# Sensores.net
KiCad netlist of a schematic drawn in Altium Designer
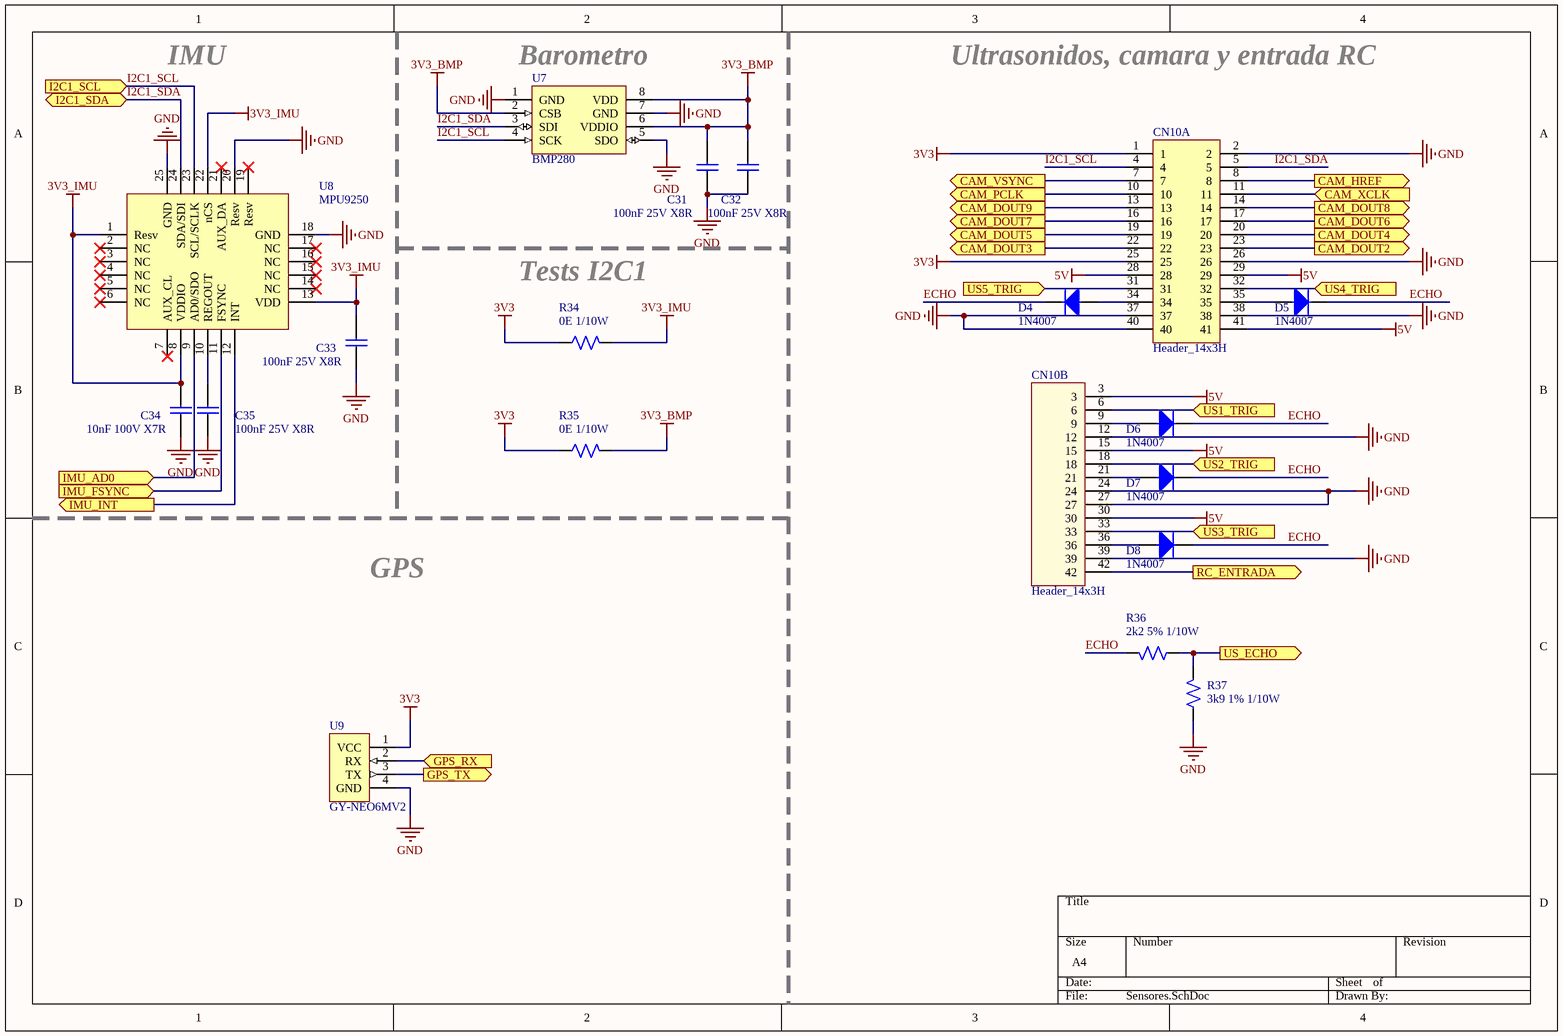
[diagram p0: Sensores.SchDoc]

(export (version "E")
  (design (tool "Eeschema 10.0.6"))
  (components
    (comp (ref "C31")
      (value "100nF 25V X8R")
      (footprint "C0603")
      (description "Capacitor de placas paralelas")
      (libsource (lib "HW_Dron_V2") (part "Capacitor"))
    )
    (comp (ref "C32")
      (value "100nF 25V X8R")
      (footprint "C0603")
      (description "Capacitor de placas paralelas")
      (libsource (lib "HW_Dron_V2") (part "Capacitor"))
    )
    (comp (ref "C33")
      (value "100nF 25V X8R")
      (footprint "C0603")
      (description "Capacitor de placas paralelas")
      (libsource (lib "HW_Dron_V2") (part "Capacitor"))
    )
    (comp (ref "C34")
      (value "10nF 100V X7R")
      (footprint "C0603")
      (description "Capacitor de placas paralelas")
      (libsource (lib "HW_Dron_V2") (part "Capacitor"))
    )
    (comp (ref "C35")
      (value "100nF 25V X8R")
      (footprint "C0603")
      (description "Capacitor de placas paralelas")
      (libsource (lib "HW_Dron_V2") (part "Capacitor"))
    )
    (comp (ref "CN10")
      (value "Header_14x3H")
      (footprint "HEADER_14x3H")
      (description "Header, 14x3-pin")
      (libsource (lib "HW_Dron_V2") (part "Header_14x3H"))
    )
    (comp (ref "D4")
      (value "1N4007")
      (footprint "SMA (DO-214AC)")
      (description "Diodo")
      (libsource (lib "HW_Dron_V2") (part "Diode"))
    )
    (comp (ref "D5")
      (value "1N4007")
      (footprint "SMA (DO-214AC)")
      (description "Diodo")
      (libsource (lib "HW_Dron_V2") (part "Diode"))
    )
    (comp (ref "D6")
      (value "1N4007")
      (footprint "SMA (DO-214AC)")
      (description "Diodo")
      (libsource (lib "HW_Dron_V2") (part "Diode"))
    )
    (comp (ref "D7")
      (value "1N4007")
      (footprint "SMA (DO-214AC)")
      (description "Diodo")
      (libsource (lib "HW_Dron_V2") (part "Diode"))
    )
    (comp (ref "D8")
      (value "1N4007")
      (footprint "SMA (DO-214AC)")
      (description "Diodo")
      (libsource (lib "HW_Dron_V2") (part "Diode"))
    )
    (comp (ref "R34")
      (value "0E 1/10W")
      (footprint "R0805")
      (description "Resistencia")
      (libsource (lib "HW_Dron_V2") (part "Resistor"))
    )
    (comp (ref "R35")
      (value "0E 1/10W")
      (footprint "R0805")
      (description "Resistencia")
      (libsource (lib "HW_Dron_V2") (part "Resistor"))
    )
    (comp (ref "R36")
      (value "2k2 5% 1/10W")
      (footprint "R0603")
      (description "Resistencia")
      (libsource (lib "HW_Dron_V2") (part "Resistor"))
    )
    (comp (ref "R37")
      (value "3k9 1% 1/10W")
      (footprint "R0603")
      (description "Resistencia")
      (libsource (lib "HW_Dron_V2") (part "Resistor"))
    )
    (comp (ref "U7")
      (value "BMP280")
      (footprint "BMP280")
      (description "Sensor de presion digital")
      (libsource (lib "HW_Dron_V2") (part "BMP280"))
    )
    (comp (ref "U8")
      (value "MPU9250")
      (footprint "MPU9250_HS")
      (description "IMU 9DOF")
      (libsource (lib "HW_Dron_V2") (part "MPU9250"))
    )
    (comp (ref "U9")
      (value "GY-NEO6MV2")
      (footprint "GY-NEO6MV2")
      (description "Modulo GPS NEO6 V2")
      (libsource (lib "HW_Dron_V2") (part "GY-NEO6MV2"))
    )
  )
  (nets
    (net (code "1") (name "/CAM_DOUT2") (class "Default")
      (node (ref "CN10") (pin "23") (pinfunction "23_23") (pintype "passive"))
    )
    (net (code "2") (name "/CAM_DOUT3") (class "Default")
      (node (ref "CN10") (pin "22") (pinfunction "22_22") (pintype "passive"))
    )
    (net (code "3") (name "/CAM_DOUT4") (class "Default")
      (node (ref "CN10") (pin "20") (pinfunction "20_20") (pintype "passive"))
    )
    (net (code "4") (name "/CAM_DOUT5") (class "Default")
      (node (ref "CN10") (pin "19") (pinfunction "19_19") (pintype "passive"))
    )
    (net (code "5") (name "/CAM_DOUT6") (class "Default")
      (node (ref "CN10") (pin "17") (pinfunction "17_17") (pintype "passive"))
    )
    (net (code "6") (name "/CAM_DOUT7") (class "Default")
      (node (ref "CN10") (pin "16") (pinfunction "16_16") (pintype "passive"))
    )
    (net (code "7") (name "/CAM_DOUT8") (class "Default")
      (node (ref "CN10") (pin "14") (pinfunction "14_14") (pintype "passive"))
    )
    (net (code "8") (name "/CAM_DOUT9") (class "Default")
      (node (ref "CN10") (pin "13") (pinfunction "13_13") (pintype "passive"))
    )
    (net (code "9") (name "/CAM_HREF") (class "Default")
      (node (ref "CN10") (pin "8") (pinfunction "8_8") (pintype "passive"))
    )
    (net (code "10") (name "/CAM_PCLK") (class "Default")
      (node (ref "CN10") (pin "10") (pinfunction "10_10") (pintype "passive"))
    )
    (net (code "11") (name "/CAM_VSYNC") (class "Default")
      (node (ref "CN10") (pin "7") (pinfunction "7_7") (pintype "passive"))
    )
    (net (code "12") (name "/CAM_XCLK") (class "Default")
      (node (ref "CN10") (pin "11") (pinfunction "11_11") (pintype "passive"))
    )
    (net (code "13") (name "/ECHO") (class "Default")
      (node (ref "D4") (pin "2") (pinfunction "2_2") (pintype "passive"))
      (node (ref "D5") (pin "2") (pinfunction "2_2") (pintype "passive"))
      (node (ref "D6") (pin "2") (pinfunction "2_2") (pintype "passive"))
      (node (ref "D7") (pin "2") (pinfunction "2_2") (pintype "passive"))
      (node (ref "D8") (pin "2") (pinfunction "2_2") (pintype "passive"))
      (node (ref "R36") (pin "2") (pinfunction "2_2") (pintype "passive"))
    )
    (net (code "14") (name "/GPS_RX") (class "Default")
      (node (ref "U9") (pin "2") (pinfunction "RX_2") (pintype "input"))
    )
    (net (code "15") (name "/GPS_TX") (class "Default")
      (node (ref "U9") (pin "3") (pinfunction "TX_3") (pintype "output"))
    )
    (net (code "16") (name "/I2C1_SCL") (class "Default")
      (node (ref "CN10") (pin "4") (pinfunction "4_4") (pintype "passive"))
      (node (ref "U7") (pin "4") (pinfunction "SCK_4") (pintype "input"))
      (node (ref "U8") (pin "23") (pinfunction "SCL/SCLK_23") (pintype "passive"))
    )
    (net (code "17") (name "/I2C1_SDA") (class "Default")
      (node (ref "CN10") (pin "5") (pinfunction "5_5") (pintype "passive"))
      (node (ref "U7") (pin "3") (pinfunction "SDI_3") (pintype "bidirectional"))
      (node (ref "U8") (pin "24") (pinfunction "SDA/SDI_24") (pintype "passive"))
    )
    (net (code "18") (name "/IMU_AD0") (class "Default")
      (node (ref "U8") (pin "9") (pinfunction "AD0/SDO_9") (pintype "passive"))
    )
    (net (code "19") (name "/IMU_FSYNC") (class "Default")
      (node (ref "U8") (pin "11") (pinfunction "FSYNC_11") (pintype "passive"))
    )
    (net (code "20") (name "/IMU_INT") (class "Default")
      (node (ref "U8") (pin "12") (pinfunction "INT_12") (pintype "passive"))
    )
    (net (code "21") (name "/RC_ENTRADA") (class "Default")
      (node (ref "CN10") (pin "42") (pinfunction "42_42") (pintype "passive"))
    )
    (net (code "22") (name "/US1_TRIG") (class "Default")
      (node (ref "CN10") (pin "6") (pinfunction "6_6") (pintype "passive"))
    )
    (net (code "23") (name "/US2_TRIG") (class "Default")
      (node (ref "CN10") (pin "18") (pinfunction "18_18") (pintype "passive"))
    )
    (net (code "24") (name "/US3_TRIG") (class "Default")
      (node (ref "CN10") (pin "33") (pinfunction "33_33") (pintype "passive"))
    )
    (net (code "25") (name "/US4_TRIG") (class "Default")
      (node (ref "CN10") (pin "32") (pinfunction "32_32") (pintype "passive"))
    )
    (net (code "26") (name "/US5_TRIG") (class "Default")
      (node (ref "CN10") (pin "31") (pinfunction "31_31") (pintype "passive"))
    )
    (net (code "27") (name "/US_ECHO") (class "Default")
      (node (ref "R36") (pin "1") (pinfunction "1_1") (pintype "passive"))
      (node (ref "R37") (pin "2") (pinfunction "2_2") (pintype "passive"))
    )
    (net (code "28") (name "3V3") (class "Default")
      (node (ref "CN10") (pin "1") (pinfunction "1_1") (pintype "passive"))
      (node (ref "CN10") (pin "25") (pinfunction "25_25") (pintype "passive"))
      (node (ref "R34") (pin "1") (pinfunction "1_1") (pintype "passive"))
      (node (ref "R35") (pin "1") (pinfunction "1_1") (pintype "passive"))
      (node (ref "U9") (pin "1") (pinfunction "VCC_1") (pintype "power_in"))
    )
    (net (code "29") (name "3V3_BMP") (class "Default")
      (node (ref "C31") (pin "1") (pinfunction "1_1") (pintype "passive"))
      (node (ref "C32") (pin "1") (pinfunction "1_1") (pintype "passive"))
      (node (ref "R35") (pin "2") (pinfunction "2_2") (pintype "passive"))
      (node (ref "U7") (pin "2") (pinfunction "CSB_2") (pintype "input"))
      (node (ref "U7") (pin "6") (pinfunction "VDDIO_6") (pintype "power_in"))
      (node (ref "U7") (pin "8") (pinfunction "VDD_8") (pintype "power_in"))
    )
    (net (code "30") (name "3V3_IMU") (class "Default")
      (node (ref "C33") (pin "1") (pinfunction "1_1") (pintype "passive"))
      (node (ref "C34") (pin "1") (pinfunction "1_1") (pintype "passive"))
      (node (ref "R34") (pin "2") (pinfunction "2_2") (pintype "passive"))
      (node (ref "U8") (pin "1") (pinfunction "Resv_1") (pintype "passive"))
      (node (ref "U8") (pin "13") (pinfunction "VDD_13") (pintype "passive"))
      (node (ref "U8") (pin "22") (pinfunction "nCS_22") (pintype "passive"))
      (node (ref "U8") (pin "8") (pinfunction "VDDIO_8") (pintype "passive"))
    )
    (net (code "31") (name "5V") (class "Default")
      (node (ref "CN10") (pin "15") (pinfunction "15_15") (pintype "passive"))
      (node (ref "CN10") (pin "28") (pinfunction "28_28") (pintype "passive"))
      (node (ref "CN10") (pin "29") (pinfunction "29_29") (pintype "passive"))
      (node (ref "CN10") (pin "3") (pinfunction "3_3") (pintype "passive"))
      (node (ref "CN10") (pin "30") (pinfunction "30_30") (pintype "passive"))
      (node (ref "CN10") (pin "41") (pinfunction "41_41") (pintype "passive"))
    )
    (net (code "32") (name "GND") (class "Default")
      (node (ref "C31") (pin "2") (pinfunction "2_2") (pintype "passive"))
      (node (ref "C32") (pin "2") (pinfunction "2_2") (pintype "passive"))
      (node (ref "C33") (pin "2") (pinfunction "2_2") (pintype "passive"))
      (node (ref "C34") (pin "2") (pinfunction "2_2") (pintype "passive"))
      (node (ref "C35") (pin "2") (pinfunction "2_2") (pintype "passive"))
      (node (ref "CN10") (pin "12") (pinfunction "12_12") (pintype "passive"))
      (node (ref "CN10") (pin "2") (pinfunction "2_2") (pintype "passive"))
      (node (ref "CN10") (pin "24") (pinfunction "24_24") (pintype "passive"))
      (node (ref "CN10") (pin "26") (pinfunction "26_26") (pintype "passive"))
      (node (ref "CN10") (pin "27") (pinfunction "27_27") (pintype "passive"))
      (node (ref "CN10") (pin "37") (pinfunction "37_37") (pintype "passive"))
      (node (ref "CN10") (pin "38") (pinfunction "38_38") (pintype "passive"))
      (node (ref "CN10") (pin "39") (pinfunction "39_39") (pintype "passive"))
      (node (ref "CN10") (pin "40") (pinfunction "40_40") (pintype "passive"))
      (node (ref "R37") (pin "1") (pinfunction "1_1") (pintype "passive"))
      (node (ref "U7") (pin "1") (pinfunction "GND_1") (pintype "power_in"))
      (node (ref "U7") (pin "5") (pinfunction "SDO_5") (pintype "bidirectional"))
      (node (ref "U7") (pin "7") (pinfunction "GND_7") (pintype "power_in"))
      (node (ref "U8") (pin "18") (pinfunction "GND_18") (pintype "passive"))
      (node (ref "U8") (pin "20") (pinfunction "Resv_20") (pintype "passive"))
      (node (ref "U8") (pin "25") (pinfunction "GND_25") (pintype "passive"))
      (node (ref "U9") (pin "4") (pinfunction "GND_4") (pintype "power_in"))
    )
    (net (code "33") (name "Net-(CN10-Pad9)") (class "Default")
      (node (ref "CN10") (pin "9") (pinfunction "9_9") (pintype "passive"))
      (node (ref "D6") (pin "1") (pinfunction "1_1") (pintype "passive"))
    )
    (net (code "34") (name "Net-(CN10-Pad21)") (class "Default")
      (node (ref "CN10") (pin "21") (pinfunction "21_21") (pintype "passive"))
      (node (ref "D7") (pin "1") (pinfunction "1_1") (pintype "passive"))
    )
    (net (code "35") (name "Net-(CN10-Pad34)") (class "Default")
      (node (ref "CN10") (pin "34") (pinfunction "34_34") (pintype "passive"))
      (node (ref "D4") (pin "1") (pinfunction "1_1") (pintype "passive"))
    )
    (net (code "36") (name "Net-(CN10-Pad35)") (class "Default")
      (node (ref "CN10") (pin "35") (pinfunction "35_35") (pintype "passive"))
      (node (ref "D5") (pin "1") (pinfunction "1_1") (pintype "passive"))
    )
    (net (code "37") (name "Net-(CN10-Pad36)") (class "Default")
      (node (ref "CN10") (pin "36") (pinfunction "36_36") (pintype "passive"))
      (node (ref "D8") (pin "1") (pinfunction "1_1") (pintype "passive"))
    )
    (net (code "38") (name "Net-(U8-REGOUT)") (class "Default")
      (node (ref "C35") (pin "1") (pinfunction "1_1") (pintype "passive"))
      (node (ref "U8") (pin "10") (pinfunction "REGOUT_10") (pintype "passive"))
    )
    (net (code "39") (name "unconnected-(U8-AUX_CL-Pad7)") (class "Default")
      (node (ref "U8") (pin "7") (pinfunction "AUX_CL_7") (pintype "passive+no_connect"))
    )
    (net (code "40") (name "unconnected-(U8-AUX_DA-Pad21)") (class "Default")
      (node (ref "U8") (pin "21") (pinfunction "AUX_DA_21") (pintype "passive+no_connect"))
    )
    (net (code "41") (name "unconnected-(U8-NC-Pad2)") (class "Default")
      (node (ref "U8") (pin "2") (pinfunction "NC_2") (pintype "passive+no_connect"))
    )
    (net (code "42") (name "unconnected-(U8-NC-Pad3)") (class "Default")
      (node (ref "U8") (pin "3") (pinfunction "NC_3") (pintype "passive+no_connect"))
    )
    (net (code "43") (name "unconnected-(U8-NC-Pad4)") (class "Default")
      (node (ref "U8") (pin "4") (pinfunction "NC_4") (pintype "passive+no_connect"))
    )
    (net (code "44") (name "unconnected-(U8-NC-Pad5)") (class "Default")
      (node (ref "U8") (pin "5") (pinfunction "NC_5") (pintype "passive+no_connect"))
    )
    (net (code "45") (name "unconnected-(U8-NC-Pad6)") (class "Default")
      (node (ref "U8") (pin "6") (pinfunction "NC_6") (pintype "passive+no_connect"))
    )
    (net (code "46") (name "unconnected-(U8-NC-Pad14)") (class "Default")
      (node (ref "U8") (pin "14") (pinfunction "NC_14") (pintype "passive+no_connect"))
    )
    (net (code "47") (name "unconnected-(U8-NC-Pad15)") (class "Default")
      (node (ref "U8") (pin "15") (pinfunction "NC_15") (pintype "passive+no_connect"))
    )
    (net (code "48") (name "unconnected-(U8-NC-Pad16)") (class "Default")
      (node (ref "U8") (pin "16") (pinfunction "NC_16") (pintype "passive+no_connect"))
    )
    (net (code "49") (name "unconnected-(U8-NC-Pad17)") (class "Default")
      (node (ref "U8") (pin "17") (pinfunction "NC_17") (pintype "passive+no_connect"))
    )
    (net (code "50") (name "unconnected-(U8-Resv-Pad19)") (class "Default")
      (node (ref "U8") (pin "19") (pinfunction "Resv_19") (pintype "passive+no_connect"))
    )
  )
)
